# ThrustAmpV1.net
KiCad netlist of a schematic drawn in EAGLE
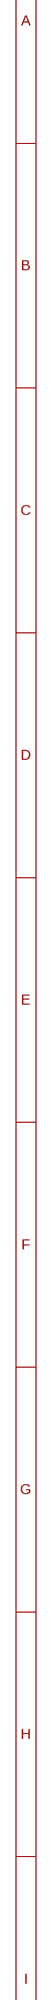
[diagram p0: schematic, sheet 1, part 1 of 2]
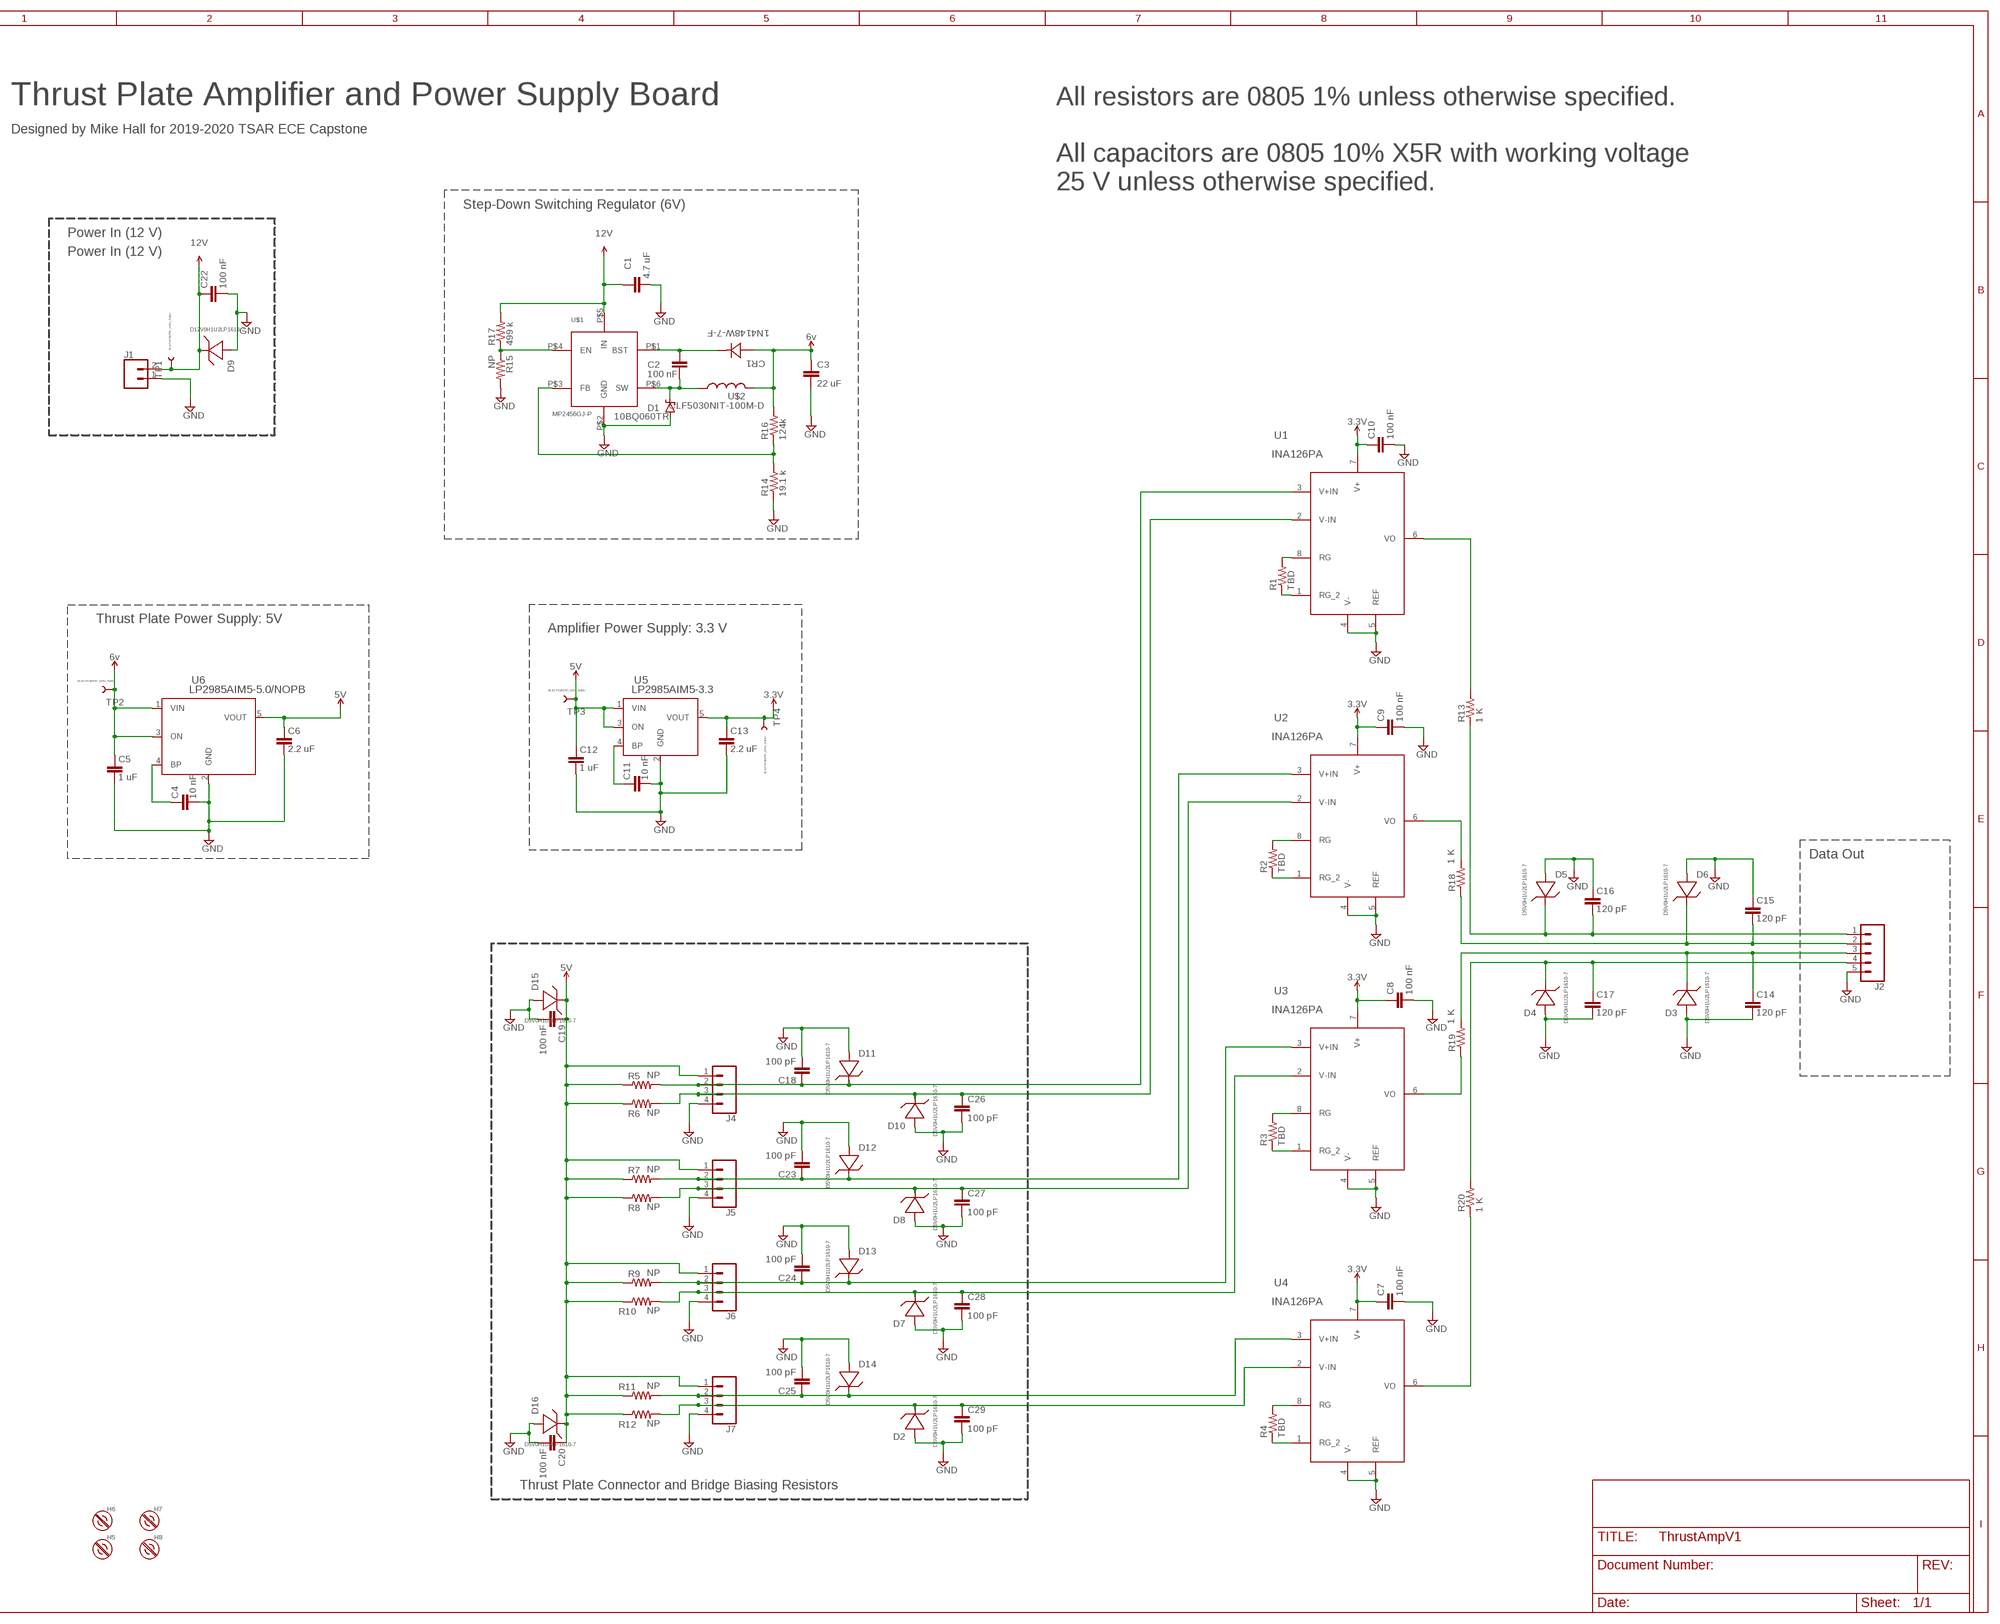
[diagram p1: schematic, sheet 1, part 2 of 2]

(export (version "E")
  (design (tool "Eeschema 10.0.6"))
  (components
    (comp (ref "C1")
      (value "4.7 uF")
      (footprint "eagle-import:C0805")
      (fields (field (name "MFR") "Samsung Electro-Mechanics") (field (name "MPN") "CL21A475KAQNNNE"))
      (libsource (lib "eagle-import") (part "C-EUC0805"))
    )
    (comp (ref "C2")
      (value "100 nF")
      (footprint "eagle-import:C0805")
      (fields (field (name "MFR") "AVX Corporation") (field (name "MPN") "08055D104KAT2A"))
      (libsource (lib "eagle-import") (part "C-EUC0805"))
    )
    (comp (ref "C3")
      (value "22 uF")
      (footprint "eagle-import:C0805")
      (fields (field (name "MFR") "Samsung Electro-Mechanics") (field (name "MPN") "CL21A226KPCLRNC"))
      (libsource (lib "eagle-import") (part "C-EUC0805"))
    )
    (comp (ref "C4")
      (value "10 nF")
      (footprint "eagle-import:C0805")
      (fields (field (name "MFR") "TDK Corporation") (field (name "MPN") "C2012X5R2E103K125AA"))
      (libsource (lib "eagle-import") (part "C-EUC0805"))
    )
    (comp (ref "C5")
      (value "1 uF")
      (footprint "eagle-import:C0805")
      (fields (field (name "MFR") "Samsung Electro-Mechanics") (field (name "MPN") "CL21A105KACLNNC"))
      (libsource (lib "eagle-import") (part "C-EUC0805"))
    )
    (comp (ref "C6")
      (value "2.2 uF")
      (footprint "eagle-import:C0805")
      (fields (field (name "MFR") "Samsung Electro-Mechanics") (field (name "MPN") "CL21A225KAFNNNG"))
      (libsource (lib "eagle-import") (part "C-EUC0805"))
    )
    (comp (ref "C7")
      (value "100 nF")
      (footprint "eagle-import:C0805K")
      (fields (field (name "MFR") "AVX Corporation") (field (name "MPN") "08055D104KAT2A"))
      (libsource (lib "eagle-import") (part "C-EUC0805K"))
    )
    (comp (ref "C8")
      (value "100 nF")
      (footprint "eagle-import:C0805K")
      (fields (field (name "MFR") "AVX Corporation") (field (name "MPN") "08055D104KAT2A"))
      (libsource (lib "eagle-import") (part "C-EUC0805K"))
    )
    (comp (ref "C9")
      (value "100 nF")
      (footprint "eagle-import:C0805K")
      (fields (field (name "MFR") "AVX Corporation") (field (name "MPN") "08055D104KAT2A"))
      (libsource (lib "eagle-import") (part "C-EUC0805K"))
    )
    (comp (ref "C10")
      (value "100 nF")
      (footprint "eagle-import:C0805K")
      (fields (field (name "MFR") "AVX Corporation") (field (name "MPN") "08055D104KAT2A"))
      (libsource (lib "eagle-import") (part "C-EUC0805K"))
    )
    (comp (ref "C11")
      (value "10 nF")
      (footprint "eagle-import:C0805")
      (fields (field (name "MFR") "TDK Corporation") (field (name "MPN") "C2012X5R2E103K125AA"))
      (libsource (lib "eagle-import") (part "C-EUC0805"))
    )
    (comp (ref "C12")
      (value "1 uF")
      (footprint "eagle-import:C0805")
      (fields (field (name "MFR") "Samsung Electro-Mechanics") (field (name "MPN") "CL21A105KACLNNC"))
      (libsource (lib "eagle-import") (part "C-EUC0805"))
    )
    (comp (ref "C13")
      (value "2.2 uF")
      (footprint "eagle-import:C0805")
      (fields (field (name "MFR") "Samsung Electro-Mechanics") (field (name "MPN") "CL21A225KAFNNNG"))
      (libsource (lib "eagle-import") (part "C-EUC0805"))
    )
    (comp (ref "C14")
      (value "120 pF")
      (footprint "eagle-import:C0805")
      (fields (field (name "MFR") "KEMET") (field (name "MPN") "C0805C121KDRACTU"))
      (libsource (lib "eagle-import") (part "C-EUC0805"))
    )
    (comp (ref "C15")
      (value "120 pF")
      (footprint "eagle-import:C0805")
      (fields (field (name "MFR") "KEMET") (field (name "MPN") "C0805C121KDRACTU"))
      (libsource (lib "eagle-import") (part "C-EUC0805"))
    )
    (comp (ref "C16")
      (value "120 pF")
      (footprint "eagle-import:C0805")
      (fields (field (name "MFR") "KEMET") (field (name "MPN") "C0805C121KDRACTU"))
      (libsource (lib "eagle-import") (part "C-EUC0805"))
    )
    (comp (ref "C17")
      (value "120 pF")
      (footprint "eagle-import:C0805")
      (fields (field (name "MFR") "KEMET") (field (name "MPN") "C0805C121KDRACTU"))
      (libsource (lib "eagle-import") (part "C-EUC0805"))
    )
    (comp (ref "C18")
      (value "100 pF")
      (footprint "eagle-import:C0805K")
      (fields (field (name "MFR") "Würth Elektronik") (field (name "MPN") "885012207054"))
      (libsource (lib "eagle-import") (part "C-EUC0805K"))
    )
    (comp (ref "C19")
      (value "100 nF")
      (footprint "eagle-import:C0805K")
      (fields (field (name "MFR") "AVX Corporation") (field (name "MPN") "08055D104KAT2A"))
      (libsource (lib "eagle-import") (part "C-EUC0805K"))
    )
    (comp (ref "C20")
      (value "100 nF")
      (footprint "eagle-import:C0805K")
      (fields (field (name "MFR") "AVX Corporation") (field (name "MPN") "08055D104KAT2A"))
      (libsource (lib "eagle-import") (part "C-EUC0805K"))
    )
    (comp (ref "C22")
      (value "100 nF")
      (footprint "eagle-import:C0805K")
      (fields (field (name "MFR") "AVX Corporation") (field (name "MPN") "08055D104KAT2A"))
      (libsource (lib "eagle-import") (part "C-EUC0805K"))
    )
    (comp (ref "C23")
      (value "100 pF")
      (footprint "eagle-import:C0805K")
      (fields (field (name "MFR") "Würth Elektronik") (field (name "MPN") "885012207054"))
      (libsource (lib "eagle-import") (part "C-EUC0805K"))
    )
    (comp (ref "C24")
      (value "100 pF")
      (footprint "eagle-import:C0805K")
      (fields (field (name "MFR") "Würth Elektronik") (field (name "MPN") "885012207054"))
      (libsource (lib "eagle-import") (part "C-EUC0805K"))
    )
    (comp (ref "C25")
      (value "100 pF")
      (footprint "eagle-import:C0805K")
      (fields (field (name "MFR") "Würth Elektronik") (field (name "MPN") "885012207054"))
      (libsource (lib "eagle-import") (part "C-EUC0805K"))
    )
    (comp (ref "C26")
      (value "100 pF")
      (footprint "eagle-import:C0805K")
      (fields (field (name "MFR") "Würth Elektronik") (field (name "MPN") "885012207054"))
      (libsource (lib "eagle-import") (part "C-EUC0805K"))
    )
    (comp (ref "C27")
      (value "100 pF")
      (footprint "eagle-import:C0805K")
      (fields (field (name "MFR") "Würth Elektronik") (field (name "MPN") "885012207054"))
      (libsource (lib "eagle-import") (part "C-EUC0805K"))
    )
    (comp (ref "C28")
      (value "100 pF")
      (footprint "eagle-import:C0805K")
      (fields (field (name "MFR") "Würth Elektronik") (field (name "MPN") "885012207054"))
      (libsource (lib "eagle-import") (part "C-EUC0805K"))
    )
    (comp (ref "C29")
      (value "100 pF")
      (footprint "eagle-import:C0805K")
      (fields (field (name "MFR") "Würth Elektronik") (field (name "MPN") "885012207054"))
      (libsource (lib "eagle-import") (part "C-EUC0805K"))
    )
    (comp (ref "CR1")
      (value "1N4148W-7-F")
      (footprint "eagle-import:SOD123")
      (fields
        (field (name "MFR") "Diodes Incorporated")
        (field (name "COPYRIGHT") "Copyright (C) 2016 Accelerated Designs. All rights reserved")
      )
      (libsource (lib "eagle-import") (part "1N4148W-7-F"))
    )
    (comp (ref "D1")
      (value "10BQ060TR")
      (footprint "eagle-import:SMB")
      (fields (field (name "MFR") "SMC Diode Solutions"))
      (libsource (lib "eagle-import") (part "SCHOTTKY-DIODESMD"))
    )
    (comp (ref "D2")
      (value "D5V0H1U2LP1610-7")
      (footprint "eagle-import:0603DIODE")
      (fields (field (name "MFR") "Diodes Incorporated"))
      (libsource (lib "eagle-import") (part "D5V0H1U2LP1610-7"))
    )
    (comp (ref "D3")
      (value "D5V0H1U2LP1610-7")
      (footprint "eagle-import:0603DIODE")
      (fields (field (name "MFR") "Diodes Incorporated"))
      (libsource (lib "eagle-import") (part "D5V0H1U2LP1610-7"))
    )
    (comp (ref "D4")
      (value "D5V0H1U2LP1610-7")
      (footprint "eagle-import:0603DIODE")
      (fields (field (name "MFR") "Diodes Incorporated"))
      (libsource (lib "eagle-import") (part "D5V0H1U2LP1610-7"))
    )
    (comp (ref "D5")
      (value "D5V0H1U2LP1610-7")
      (footprint "eagle-import:0603DIODE")
      (fields (field (name "MFR") "Diodes Incorporated"))
      (libsource (lib "eagle-import") (part "D5V0H1U2LP1610-7"))
    )
    (comp (ref "D6")
      (value "D5V0H1U2LP1610-7")
      (footprint "eagle-import:0603DIODE")
      (fields (field (name "MFR") "Diodes Incorporated"))
      (libsource (lib "eagle-import") (part "D5V0H1U2LP1610-7"))
    )
    (comp (ref "D7")
      (value "D5V0H1U2LP1610-7")
      (footprint "eagle-import:0603DIODE")
      (fields (field (name "MFR") "Diodes Incorporated"))
      (libsource (lib "eagle-import") (part "D5V0H1U2LP1610-7"))
    )
    (comp (ref "D8")
      (value "D5V0H1U2LP1610-7")
      (footprint "eagle-import:0603DIODE")
      (fields (field (name "MFR") "Diodes Incorporated"))
      (libsource (lib "eagle-import") (part "D5V0H1U2LP1610-7"))
    )
    (comp (ref "D9")
      (value "D12V0H1U2LP1610-70603DIODE12V")
      (footprint "eagle-import:0603DIODE")
      (fields (field (name "MFR") "Diodes Incorporated") (field (name "MPN") "D12V0H1U2LP1610-7"))
      (libsource (lib "eagle-import") (part "D12V0H1U2LP1610-70603DIODE12V"))
    )
    (comp (ref "D10")
      (value "D5V0H1U2LP1610-7")
      (footprint "eagle-import:0603DIODE")
      (fields (field (name "MFR") "Diodes Incorporated"))
      (libsource (lib "eagle-import") (part "D5V0H1U2LP1610-7"))
    )
    (comp (ref "D11")
      (value "D5V0H1U2LP1610-7")
      (footprint "eagle-import:0603DIODE")
      (fields (field (name "MFR") "Diodes Incorporated"))
      (libsource (lib "eagle-import") (part "D5V0H1U2LP1610-7"))
    )
    (comp (ref "D12")
      (value "D5V0H1U2LP1610-7")
      (footprint "eagle-import:0603DIODE")
      (fields (field (name "MFR") "Diodes Incorporated"))
      (libsource (lib "eagle-import") (part "D5V0H1U2LP1610-7"))
    )
    (comp (ref "D13")
      (value "D5V0H1U2LP1610-7")
      (footprint "eagle-import:0603DIODE")
      (fields (field (name "MFR") "Diodes Incorporated"))
      (libsource (lib "eagle-import") (part "D5V0H1U2LP1610-7"))
    )
    (comp (ref "D14")
      (value "D5V0H1U2LP1610-7")
      (footprint "eagle-import:0603DIODE")
      (fields (field (name "MFR") "Diodes Incorporated"))
      (libsource (lib "eagle-import") (part "D5V0H1U2LP1610-7"))
    )
    (comp (ref "D15")
      (value "D5V0H1U2LP1610-7")
      (footprint "eagle-import:0603DIODE")
      (fields (field (name "MFR") "Diodes Incorporated"))
      (libsource (lib "eagle-import") (part "D5V0H1U2LP1610-7"))
    )
    (comp (ref "D16")
      (value "D5V0H1U2LP1610-7")
      (footprint "eagle-import:0603DIODE")
      (fields (field (name "MFR") "Diodes Incorporated"))
      (libsource (lib "eagle-import") (part "D5V0H1U2LP1610-7"))
    )
    (comp (ref "H5")
      (value "#4-BARE_MOUNTING_HOLE/.300")
      (footprint "eagle-import:#4_.300-BARE+STD_NUT_OR_STAR_WASHER")
      (libsource (lib "eagle-import") (part "#4-BARE_MOUNTING_HOLE/.300"))
    )
    (comp (ref "H6")
      (value "#4-BARE_MOUNTING_HOLE/.300")
      (footprint "eagle-import:#4_.300-BARE+STD_NUT_OR_STAR_WASHER")
      (libsource (lib "eagle-import") (part "#4-BARE_MOUNTING_HOLE/.300"))
    )
    (comp (ref "H7")
      (value "#4-BARE_MOUNTING_HOLE/.300")
      (footprint "eagle-import:#4_.300-BARE+STD_NUT_OR_STAR_WASHER")
      (libsource (lib "eagle-import") (part "#4-BARE_MOUNTING_HOLE/.300"))
    )
    (comp (ref "H8")
      (value "#4-BARE_MOUNTING_HOLE/.300")
      (footprint "eagle-import:#4_.300-BARE+STD_NUT_OR_STAR_WASHER")
      (libsource (lib "eagle-import") (part "#4-BARE_MOUNTING_HOLE/.300"))
    )
    (comp (ref "J1")
      (value "CONN_02PTH3")
      (footprint "eagle-import:1X02_LONGPADS")
      (fields (field (name "MFR") "Molex") (field (name "MPN") "22232021"))
      (libsource (lib "eagle-import") (part "CONN_02PTH3"))
    )
    (comp (ref "J2")
      (value "CONN_05PTH_LONGPADS")
      (footprint "eagle-import:1X05_LONGPADS")
      (fields (field (name "MFR") "Molex") (field (name "MPN") "0022232051"))
      (libsource (lib "eagle-import") (part "CONN_05PTH_LONGPADS"))
    )
    (comp (ref "J4")
      (value "CONN_04")
      (footprint "eagle-import:1X04")
      (fields (field (name "MFR") "Molex") (field (name "MPN") "0022232041"))
      (libsource (lib "eagle-import") (part "CONN_04"))
    )
    (comp (ref "J5")
      (value "CONN_04")
      (footprint "eagle-import:1X04")
      (fields (field (name "MFR") "Molex") (field (name "MPN") "0022232041"))
      (libsource (lib "eagle-import") (part "CONN_04"))
    )
    (comp (ref "J6")
      (value "CONN_04")
      (footprint "eagle-import:1X04")
      (fields (field (name "MFR") "Molex") (field (name "MPN") "0022232041"))
      (libsource (lib "eagle-import") (part "CONN_04"))
    )
    (comp (ref "J7")
      (value "CONN_04")
      (footprint "eagle-import:1X04")
      (fields (field (name "MFR") "Molex") (field (name "MPN") "0022232041"))
      (libsource (lib "eagle-import") (part "CONN_04"))
    )
    (comp (ref "R1")
      (value "TBD")
      (footprint "eagle-import:R0805")
      (libsource (lib "eagle-import") (part "R-US_R0805"))
    )
    (comp (ref "R2")
      (value "TBD")
      (footprint "eagle-import:R0805")
      (libsource (lib "eagle-import") (part "R-US_R0805"))
    )
    (comp (ref "R3")
      (value "TBD")
      (footprint "eagle-import:R0805")
      (libsource (lib "eagle-import") (part "R-US_R0805"))
    )
    (comp (ref "R4")
      (value "TBD")
      (footprint "eagle-import:R0805")
      (libsource (lib "eagle-import") (part "R-US_R0805"))
    )
    (comp (ref "R5")
      (value "NP")
      (footprint "eagle-import:0207_5V")
      (libsource (lib "eagle-import") (part "R-US_0207/5V"))
    )
    (comp (ref "R6")
      (value "NP")
      (footprint "eagle-import:0207_5V")
      (libsource (lib "eagle-import") (part "R-US_0207/5V"))
    )
    (comp (ref "R7")
      (value "NP")
      (footprint "eagle-import:0207_5V")
      (libsource (lib "eagle-import") (part "R-US_0207/5V"))
    )
    (comp (ref "R8")
      (value "NP")
      (footprint "eagle-import:0207_5V")
      (libsource (lib "eagle-import") (part "R-US_0207/5V"))
    )
    (comp (ref "R9")
      (value "NP")
      (footprint "eagle-import:0207_5V")
      (libsource (lib "eagle-import") (part "R-US_0207/5V"))
    )
    (comp (ref "R10")
      (value "NP")
      (footprint "eagle-import:0207_5V")
      (libsource (lib "eagle-import") (part "R-US_0207/5V"))
    )
    (comp (ref "R11")
      (value "NP")
      (footprint "eagle-import:0207_5V")
      (libsource (lib "eagle-import") (part "R-US_0207/5V"))
    )
    (comp (ref "R12")
      (value "NP")
      (footprint "eagle-import:0207_5V")
      (libsource (lib "eagle-import") (part "R-US_0207/5V"))
    )
    (comp (ref "R13")
      (value "1 K")
      (footprint "eagle-import:R0805")
      (fields (field (name "MFR") "Yageo") (field (name "MPN") "RC0805FR-071KL"))
      (libsource (lib "eagle-import") (part "R-US_R0805"))
    )
    (comp (ref "R14")
      (value "19.1 k")
      (footprint "eagle-import:R0805")
      (fields (field (name "MFR") "Stackpole Electronics Inc") (field (name "MPN") "RNCP0805FTD19K1"))
      (libsource (lib "eagle-import") (part "R-US_R0805"))
    )
    (comp (ref "R15")
      (value "NP")
      (footprint "eagle-import:R0805")
      (libsource (lib "eagle-import") (part "R-US_R0805"))
    )
    (comp (ref "R16")
      (value "124k")
      (footprint "eagle-import:R0805")
      (fields (field (name "MFR") "KOA Speer Electronics, Inc.") (field (name "MPN") "RK73H2ATTD1243F"))
      (libsource (lib "eagle-import") (part "R-US_R0805"))
    )
    (comp (ref "R17")
      (value "499 k")
      (footprint "eagle-import:R0805")
      (fields (field (name "MFR") "KOA Speer Electronics, Inc.") (field (name "MPN") "RK73H2ATTD4993F"))
      (libsource (lib "eagle-import") (part "R-US_R0805"))
    )
    (comp (ref "R18")
      (value "1 K")
      (footprint "eagle-import:R0805")
      (fields (field (name "MFR") "Yageo") (field (name "MPN") "RC0805FR-071KL"))
      (libsource (lib "eagle-import") (part "R-US_R0805"))
    )
    (comp (ref "R19")
      (value "1 K")
      (footprint "eagle-import:R0805")
      (fields (field (name "MFR") "Yageo") (field (name "MPN") "RC0805FR-071KL"))
      (libsource (lib "eagle-import") (part "R-US_R0805"))
    )
    (comp (ref "R20")
      (value "1 K")
      (footprint "eagle-import:R0805")
      (fields (field (name "MFR") "Yageo") (field (name "MPN") "RC0805FR-071KL"))
      (libsource (lib "eagle-import") (part "R-US_R0805"))
    )
    (comp (ref "TP1")
      (value "TEST-POINTTP_15TH_THRU")
      (footprint "eagle-import:TP_15TH")
      (libsource (lib "eagle-import") (part "TEST-POINTTP_15TH_THRU"))
    )
    (comp (ref "TP2")
      (value "TEST-POINTTP_15TH_THRU")
      (footprint "eagle-import:TP_15TH")
      (libsource (lib "eagle-import") (part "TEST-POINTTP_15TH_THRU"))
    )
    (comp (ref "TP3")
      (value "TEST-POINTTP_15TH_THRU")
      (footprint "eagle-import:TP_15TH")
      (libsource (lib "eagle-import") (part "TEST-POINTTP_15TH_THRU"))
    )
    (comp (ref "TP4")
      (value "TEST-POINTTP_15TH_THRU")
      (footprint "eagle-import:TP_15TH")
      (libsource (lib "eagle-import") (part "TEST-POINTTP_15TH_THRU"))
    )
    (comp (ref "U$1")
      (value "MP2456GJ-P")
      (footprint "eagle-import:SOT6")
      (fields (field (name "MFR") "Monolithic Power Systems Inc."))
      (libsource (lib "eagle-import") (part "MP2456GJ-P"))
    )
    (comp (ref "U$2")
      (value "CLF5030NIT-100M-D")
      (footprint "eagle-import:0.209_LX0.197_W(5.30MMX5.00MM)")
      (fields (field (name "MFR") "TDK Corporation"))
      (libsource (lib "eagle-import") (part "CLF5030NIT-100M-D"))
    )
    (comp (ref "U1")
      (value "INA126PA")
      (footprint "eagle-import:P8")
      (fields (field (name "MFR") "Texas Instruments"))
      (libsource (lib "eagle-import") (part "INA126PA"))
    )
    (comp (ref "U2")
      (value "INA126PA")
      (footprint "eagle-import:P8")
      (fields (field (name "MFR") "Texas Instruments"))
      (libsource (lib "eagle-import") (part "INA126PA"))
    )
    (comp (ref "U3")
      (value "INA126PA")
      (footprint "eagle-import:P8")
      (fields (field (name "MFR") "Texas Instruments"))
      (libsource (lib "eagle-import") (part "INA126PA"))
    )
    (comp (ref "U4")
      (value "INA126PA")
      (footprint "eagle-import:P8")
      (fields (field (name "MFR") "Texas Instruments"))
      (libsource (lib "eagle-import") (part "INA126PA"))
    )
    (comp (ref "U5")
      (value "LP2985AIM5-3.3")
      (footprint "eagle-import:MF05A")
      (fields (field (name "MFR") "Texas Instruments") (field (name "MPN") "LP2985AIM5-3.3/NOPB"))
      (libsource (lib "eagle-import") (part "LP2985AIM5-3.3"))
    )
    (comp (ref "U6")
      (value "LP2985AIM5-5.0/NOPB")
      (footprint "eagle-import:MF05A")
      (fields (field (name "MFR") "Texas Instruments"))
      (libsource (lib "eagle-import") (part "LP2985AIM5-5.0/NOPB"))
    )
  )
  (nets
    (net (code "1") (name "3.3V") (class "Default")
      (node (ref "C10") (pin "1") (pinfunction "1_1") (pintype "passive"))
      (node (ref "C13") (pin "1") (pinfunction "1_1") (pintype "passive"))
      (node (ref "C7") (pin "1") (pinfunction "1_1") (pintype "passive"))
      (node (ref "C8") (pin "1") (pinfunction "1_1") (pintype "passive"))
      (node (ref "C9") (pin "1") (pinfunction "1_1") (pintype "passive"))
      (node (ref "TP4") (pin "P$1") (pinfunction "1_P$1") (pintype "bidirectional"))
      (node (ref "U1") (pin "7") (pinfunction "V+_7") (pintype "power_in"))
      (node (ref "U2") (pin "7") (pinfunction "V+_7") (pintype "power_in"))
      (node (ref "U3") (pin "7") (pinfunction "V+_7") (pintype "power_in"))
      (node (ref "U4") (pin "7") (pinfunction "V+_7") (pintype "power_in"))
      (node (ref "U5") (pin "5") (pinfunction "VOUT_5") (pintype "power_in"))
    )
    (net (code "2") (name "5V") (class "Default")
      (node (ref "C12") (pin "1") (pinfunction "1_1") (pintype "passive"))
      (node (ref "C19") (pin "1") (pinfunction "1_1") (pintype "passive"))
      (node (ref "C20") (pin "1") (pinfunction "1_1") (pintype "passive"))
      (node (ref "C6") (pin "1") (pinfunction "1_1") (pintype "passive"))
      (node (ref "D15") (pin "P$2") (pinfunction "P$2_P$2") (pintype "passive"))
      (node (ref "D16") (pin "P$2") (pinfunction "P$2_P$2") (pintype "passive"))
      (node (ref "J4") (pin "1") (pinfunction "1_1") (pintype "passive"))
      (node (ref "J5") (pin "1") (pinfunction "1_1") (pintype "passive"))
      (node (ref "J6") (pin "1") (pinfunction "1_1") (pintype "passive"))
      (node (ref "J7") (pin "1") (pinfunction "1_1") (pintype "passive"))
      (node (ref "R10") (pin "1") (pinfunction "1_1") (pintype "passive"))
      (node (ref "R11") (pin "1") (pinfunction "1_1") (pintype "passive"))
      (node (ref "R12") (pin "1") (pinfunction "1_1") (pintype "passive"))
      (node (ref "R5") (pin "1") (pinfunction "1_1") (pintype "passive"))
      (node (ref "R6") (pin "1") (pinfunction "1_1") (pintype "passive"))
      (node (ref "R7") (pin "1") (pinfunction "1_1") (pintype "passive"))
      (node (ref "R8") (pin "1") (pinfunction "1_1") (pintype "passive"))
      (node (ref "R9") (pin "1") (pinfunction "1_1") (pintype "passive"))
      (node (ref "TP3") (pin "P$1") (pinfunction "1_P$1") (pintype "bidirectional"))
      (node (ref "U5") (pin "1") (pinfunction "VIN_1") (pintype "power_in"))
      (node (ref "U5") (pin "3") (pinfunction "ON_3") (pintype "input"))
      (node (ref "U6") (pin "5") (pinfunction "VOUT_5") (pintype "power_in"))
    )
    (net (code "3") (name "6v") (class "Default")
      (node (ref "C3") (pin "1") (pinfunction "1_1") (pintype "passive"))
      (node (ref "C5") (pin "1") (pinfunction "1_1") (pintype "passive"))
      (node (ref "CR1") (pin "2") (pinfunction "2_2") (pintype "passive"))
      (node (ref "R16") (pin "2") (pinfunction "2_2") (pintype "passive"))
      (node (ref "TP2") (pin "P$1") (pinfunction "1_P$1") (pintype "bidirectional"))
      (node (ref "U$2") (pin "2") (pinfunction "2_2") (pintype "passive"))
      (node (ref "U6") (pin "1") (pinfunction "VIN_1") (pintype "input"))
      (node (ref "U6") (pin "3") (pinfunction "ON_3") (pintype "passive"))
    )
    (net (code "4") (name "12V") (class "Default")
      (node (ref "C1") (pin "1") (pinfunction "1_1") (pintype "passive"))
      (node (ref "C22") (pin "1") (pinfunction "1_1") (pintype "passive"))
      (node (ref "D9") (pin "P$2") (pinfunction "P$2_P$2") (pintype "passive"))
      (node (ref "J1") (pin "2") (pinfunction "2_2") (pintype "passive"))
      (node (ref "R17") (pin "2") (pinfunction "2_2") (pintype "passive"))
      (node (ref "TP1") (pin "P$1") (pinfunction "1_P$1") (pintype "bidirectional"))
      (node (ref "U$1") (pin "P$5") (pinfunction "IN_P$5") (pintype "power_in"))
    )
    (net (code "5") (name "GND") (class "Default")
      (node (ref "C1") (pin "2") (pinfunction "2_2") (pintype "passive"))
      (node (ref "C10") (pin "2") (pinfunction "2_2") (pintype "passive"))
      (node (ref "C11") (pin "2") (pinfunction "2_2") (pintype "passive"))
      (node (ref "C12") (pin "2") (pinfunction "2_2") (pintype "passive"))
      (node (ref "C13") (pin "2") (pinfunction "2_2") (pintype "passive"))
      (node (ref "C14") (pin "2") (pinfunction "2_2") (pintype "passive"))
      (node (ref "C15") (pin "1") (pinfunction "1_1") (pintype "passive"))
      (node (ref "C16") (pin "1") (pinfunction "1_1") (pintype "passive"))
      (node (ref "C17") (pin "2") (pinfunction "2_2") (pintype "passive"))
      (node (ref "C18") (pin "2") (pinfunction "2_2") (pintype "passive"))
      (node (ref "C19") (pin "2") (pinfunction "2_2") (pintype "passive"))
      (node (ref "C20") (pin "2") (pinfunction "2_2") (pintype "passive"))
      (node (ref "C22") (pin "2") (pinfunction "2_2") (pintype "passive"))
      (node (ref "C23") (pin "2") (pinfunction "2_2") (pintype "passive"))
      (node (ref "C24") (pin "2") (pinfunction "2_2") (pintype "passive"))
      (node (ref "C25") (pin "2") (pinfunction "2_2") (pintype "passive"))
      (node (ref "C26") (pin "2") (pinfunction "2_2") (pintype "passive"))
      (node (ref "C27") (pin "2") (pinfunction "2_2") (pintype "passive"))
      (node (ref "C28") (pin "2") (pinfunction "2_2") (pintype "passive"))
      (node (ref "C29") (pin "2") (pinfunction "2_2") (pintype "passive"))
      (node (ref "C3") (pin "2") (pinfunction "2_2") (pintype "passive"))
      (node (ref "C4") (pin "2") (pinfunction "2_2") (pintype "passive"))
      (node (ref "C5") (pin "2") (pinfunction "2_2") (pintype "passive"))
      (node (ref "C6") (pin "2") (pinfunction "2_2") (pintype "passive"))
      (node (ref "C7") (pin "2") (pinfunction "2_2") (pintype "passive"))
      (node (ref "C8") (pin "2") (pinfunction "2_2") (pintype "passive"))
      (node (ref "C9") (pin "2") (pinfunction "2_2") (pintype "passive"))
      (node (ref "D1") (pin "A") (pinfunction "A_A") (pintype "passive"))
      (node (ref "D10") (pin "P$1") (pinfunction "P$1_P$1") (pintype "passive"))
      (node (ref "D11") (pin "P$1") (pinfunction "P$1_P$1") (pintype "passive"))
      (node (ref "D12") (pin "P$1") (pinfunction "P$1_P$1") (pintype "passive"))
      (node (ref "D13") (pin "P$1") (pinfunction "P$1_P$1") (pintype "passive"))
      (node (ref "D14") (pin "P$1") (pinfunction "P$1_P$1") (pintype "passive"))
      (node (ref "D15") (pin "P$1") (pinfunction "P$1_P$1") (pintype "passive"))
      (node (ref "D16") (pin "P$1") (pinfunction "P$1_P$1") (pintype "passive"))
      (node (ref "D2") (pin "P$1") (pinfunction "P$1_P$1") (pintype "passive"))
      (node (ref "D3") (pin "P$1") (pinfunction "P$1_P$1") (pintype "passive"))
      (node (ref "D4") (pin "P$1") (pinfunction "P$1_P$1") (pintype "passive"))
      (node (ref "D5") (pin "P$1") (pinfunction "P$1_P$1") (pintype "passive"))
      (node (ref "D6") (pin "P$1") (pinfunction "P$1_P$1") (pintype "passive"))
      (node (ref "D7") (pin "P$1") (pinfunction "P$1_P$1") (pintype "passive"))
      (node (ref "D8") (pin "P$1") (pinfunction "P$1_P$1") (pintype "passive"))
      (node (ref "D9") (pin "P$1") (pinfunction "P$1_P$1") (pintype "passive"))
      (node (ref "J1") (pin "1") (pinfunction "1_1") (pintype "passive"))
      (node (ref "J2") (pin "5") (pinfunction "5_5") (pintype "passive"))
      (node (ref "J4") (pin "4") (pinfunction "4_4") (pintype "passive"))
      (node (ref "J5") (pin "4") (pinfunction "4_4") (pintype "passive"))
      (node (ref "J6") (pin "4") (pinfunction "4_4") (pintype "passive"))
      (node (ref "J7") (pin "4") (pinfunction "4_4") (pintype "passive"))
      (node (ref "R14") (pin "1") (pinfunction "1_1") (pintype "passive"))
      (node (ref "R15") (pin "2") (pinfunction "2_2") (pintype "passive"))
      (node (ref "U$1") (pin "P$2") (pinfunction "GND_P$2") (pintype "bidirectional"))
      (node (ref "U1") (pin "4") (pinfunction "V-_4") (pintype "power_in"))
      (node (ref "U1") (pin "5") (pinfunction "REF_5") (pintype "passive"))
      (node (ref "U2") (pin "4") (pinfunction "V-_4") (pintype "power_in"))
      (node (ref "U2") (pin "5") (pinfunction "REF_5") (pintype "passive"))
      (node (ref "U3") (pin "4") (pinfunction "V-_4") (pintype "power_in"))
      (node (ref "U3") (pin "5") (pinfunction "REF_5") (pintype "passive"))
      (node (ref "U4") (pin "4") (pinfunction "V-_4") (pintype "power_in"))
      (node (ref "U4") (pin "5") (pinfunction "REF_5") (pintype "passive"))
      (node (ref "U5") (pin "2") (pinfunction "GND_2") (pintype "passive"))
      (node (ref "U6") (pin "2") (pinfunction "GND_2") (pintype "passive"))
    )
    (net (code "6") (name "Net-(C14-Pad1)") (class "Default")
      (node (ref "C14") (pin "1") (pinfunction "1_1") (pintype "passive"))
      (node (ref "D3") (pin "P$2") (pinfunction "P$2_P$2") (pintype "passive"))
      (node (ref "J2") (pin "3") (pinfunction "3_3") (pintype "passive"))
      (node (ref "R19") (pin "2") (pinfunction "2_2") (pintype "passive"))
    )
    (net (code "7") (name "Net-(C15-Pad2)") (class "Default")
      (node (ref "C15") (pin "2") (pinfunction "2_2") (pintype "passive"))
      (node (ref "D6") (pin "P$2") (pinfunction "P$2_P$2") (pintype "passive"))
      (node (ref "J2") (pin "2") (pinfunction "2_2") (pintype "passive"))
      (node (ref "R18") (pin "1") (pinfunction "1_1") (pintype "passive"))
    )
    (net (code "8") (name "Net-(C16-Pad2)") (class "Default")
      (node (ref "C16") (pin "2") (pinfunction "2_2") (pintype "passive"))
      (node (ref "D5") (pin "P$2") (pinfunction "P$2_P$2") (pintype "passive"))
      (node (ref "J2") (pin "1") (pinfunction "1_1") (pintype "passive"))
      (node (ref "R13") (pin "1") (pinfunction "1_1") (pintype "passive"))
    )
    (net (code "9") (name "Net-(C17-Pad1)") (class "Default")
      (node (ref "C17") (pin "1") (pinfunction "1_1") (pintype "passive"))
      (node (ref "D4") (pin "P$2") (pinfunction "P$2_P$2") (pintype "passive"))
      (node (ref "J2") (pin "4") (pinfunction "4_4") (pintype "passive"))
      (node (ref "R20") (pin "2") (pinfunction "2_2") (pintype "passive"))
    )
    (net (code "10") (name "Net-(U$1-BST)") (class "Default")
      (node (ref "C2") (pin "1") (pinfunction "1_1") (pintype "passive"))
      (node (ref "CR1") (pin "1") (pinfunction "1_1") (pintype "passive"))
      (node (ref "U$1") (pin "P$1") (pinfunction "BST_P$1") (pintype "bidirectional"))
    )
    (net (code "11") (name "Net-(U$1-EN)") (class "Default")
      (node (ref "R15") (pin "1") (pinfunction "1_1") (pintype "passive"))
      (node (ref "R17") (pin "1") (pinfunction "1_1") (pintype "passive"))
      (node (ref "U$1") (pin "P$4") (pinfunction "EN_P$4") (pintype "input"))
    )
    (net (code "12") (name "Net-(U$1-FB)") (class "Default")
      (node (ref "R14") (pin "2") (pinfunction "2_2") (pintype "passive"))
      (node (ref "R16") (pin "1") (pinfunction "1_1") (pintype "passive"))
      (node (ref "U$1") (pin "P$3") (pinfunction "FB_P$3") (pintype "bidirectional"))
    )
    (net (code "13") (name "Net-(U$1-SW)") (class "Default")
      (node (ref "C2") (pin "2") (pinfunction "2_2") (pintype "passive"))
      (node (ref "D1") (pin "C") (pinfunction "C_C") (pintype "passive"))
      (node (ref "U$1") (pin "P$6") (pinfunction "SW_P$6") (pintype "bidirectional"))
      (node (ref "U$2") (pin "1") (pinfunction "1_1") (pintype "passive"))
    )
    (net (code "14") (name "Net-(U1-RG)") (class "Default")
      (node (ref "R1") (pin "2") (pinfunction "2_2") (pintype "passive"))
      (node (ref "U1") (pin "8") (pinfunction "RG_8") (pintype "passive"))
    )
    (net (code "15") (name "Net-(U1-RG_2)") (class "Default")
      (node (ref "R1") (pin "1") (pinfunction "1_1") (pintype "passive"))
      (node (ref "U1") (pin "1") (pinfunction "RG_2_1") (pintype "passive"))
    )
    (net (code "16") (name "Net-(U1-V+IN)") (class "Default")
      (node (ref "C18") (pin "1") (pinfunction "1_1") (pintype "passive"))
      (node (ref "D11") (pin "P$2") (pinfunction "P$2_P$2") (pintype "passive"))
      (node (ref "J4") (pin "2") (pinfunction "2_2") (pintype "passive"))
      (node (ref "R5") (pin "2") (pinfunction "2_2") (pintype "passive"))
      (node (ref "U1") (pin "3") (pinfunction "V+IN_3") (pintype "input"))
    )
    (net (code "17") (name "Net-(U1-V-IN)") (class "Default")
      (node (ref "C26") (pin "1") (pinfunction "1_1") (pintype "passive"))
      (node (ref "D10") (pin "P$2") (pinfunction "P$2_P$2") (pintype "passive"))
      (node (ref "J4") (pin "3") (pinfunction "3_3") (pintype "passive"))
      (node (ref "R6") (pin "2") (pinfunction "2_2") (pintype "passive"))
      (node (ref "U1") (pin "2") (pinfunction "V-IN_2") (pintype "input"))
    )
    (net (code "18") (name "Net-(U1-VO)") (class "Default")
      (node (ref "R13") (pin "2") (pinfunction "2_2") (pintype "passive"))
      (node (ref "U1") (pin "6") (pinfunction "VO_6") (pintype "output"))
    )
    (net (code "19") (name "Net-(U2-RG)") (class "Default")
      (node (ref "R2") (pin "2") (pinfunction "2_2") (pintype "passive"))
      (node (ref "U2") (pin "8") (pinfunction "RG_8") (pintype "passive"))
    )
    (net (code "20") (name "Net-(U2-RG_2)") (class "Default")
      (node (ref "R2") (pin "1") (pinfunction "1_1") (pintype "passive"))
      (node (ref "U2") (pin "1") (pinfunction "RG_2_1") (pintype "passive"))
    )
    (net (code "21") (name "Net-(U2-V+IN)") (class "Default")
      (node (ref "C23") (pin "1") (pinfunction "1_1") (pintype "passive"))
      (node (ref "D12") (pin "P$2") (pinfunction "P$2_P$2") (pintype "passive"))
      (node (ref "J5") (pin "2") (pinfunction "2_2") (pintype "passive"))
      (node (ref "R7") (pin "2") (pinfunction "2_2") (pintype "passive"))
      (node (ref "U2") (pin "3") (pinfunction "V+IN_3") (pintype "input"))
    )
    (net (code "22") (name "Net-(U2-V-IN)") (class "Default")
      (node (ref "C27") (pin "1") (pinfunction "1_1") (pintype "passive"))
      (node (ref "D8") (pin "P$2") (pinfunction "P$2_P$2") (pintype "passive"))
      (node (ref "J5") (pin "3") (pinfunction "3_3") (pintype "passive"))
      (node (ref "R8") (pin "2") (pinfunction "2_2") (pintype "passive"))
      (node (ref "U2") (pin "2") (pinfunction "V-IN_2") (pintype "input"))
    )
    (net (code "23") (name "Net-(U2-VO)") (class "Default")
      (node (ref "R18") (pin "2") (pinfunction "2_2") (pintype "passive"))
      (node (ref "U2") (pin "6") (pinfunction "VO_6") (pintype "output"))
    )
    (net (code "24") (name "Net-(U3-RG)") (class "Default")
      (node (ref "R3") (pin "2") (pinfunction "2_2") (pintype "passive"))
      (node (ref "U3") (pin "8") (pinfunction "RG_8") (pintype "passive"))
    )
    (net (code "25") (name "Net-(U3-RG_2)") (class "Default")
      (node (ref "R3") (pin "1") (pinfunction "1_1") (pintype "passive"))
      (node (ref "U3") (pin "1") (pinfunction "RG_2_1") (pintype "passive"))
    )
    (net (code "26") (name "Net-(U3-V+IN)") (class "Default")
      (node (ref "C24") (pin "1") (pinfunction "1_1") (pintype "passive"))
      (node (ref "D13") (pin "P$2") (pinfunction "P$2_P$2") (pintype "passive"))
      (node (ref "J6") (pin "2") (pinfunction "2_2") (pintype "passive"))
      (node (ref "R9") (pin "2") (pinfunction "2_2") (pintype "passive"))
      (node (ref "U3") (pin "3") (pinfunction "V+IN_3") (pintype "input"))
    )
    (net (code "27") (name "Net-(U3-V-IN)") (class "Default")
      (node (ref "C28") (pin "1") (pinfunction "1_1") (pintype "passive"))
      (node (ref "D7") (pin "P$2") (pinfunction "P$2_P$2") (pintype "passive"))
      (node (ref "J6") (pin "3") (pinfunction "3_3") (pintype "passive"))
      (node (ref "R10") (pin "2") (pinfunction "2_2") (pintype "passive"))
      (node (ref "U3") (pin "2") (pinfunction "V-IN_2") (pintype "input"))
    )
    (net (code "28") (name "Net-(U3-VO)") (class "Default")
      (node (ref "R19") (pin "1") (pinfunction "1_1") (pintype "passive"))
      (node (ref "U3") (pin "6") (pinfunction "VO_6") (pintype "output"))
    )
    (net (code "29") (name "Net-(U4-RG)") (class "Default")
      (node (ref "R4") (pin "2") (pinfunction "2_2") (pintype "passive"))
      (node (ref "U4") (pin "8") (pinfunction "RG_8") (pintype "passive"))
    )
    (net (code "30") (name "Net-(U4-RG_2)") (class "Default")
      (node (ref "R4") (pin "1") (pinfunction "1_1") (pintype "passive"))
      (node (ref "U4") (pin "1") (pinfunction "RG_2_1") (pintype "passive"))
    )
    (net (code "31") (name "Net-(U4-V+IN)") (class "Default")
      (node (ref "C25") (pin "1") (pinfunction "1_1") (pintype "passive"))
      (node (ref "D14") (pin "P$2") (pinfunction "P$2_P$2") (pintype "passive"))
      (node (ref "J7") (pin "2") (pinfunction "2_2") (pintype "passive"))
      (node (ref "R11") (pin "2") (pinfunction "2_2") (pintype "passive"))
      (node (ref "U4") (pin "3") (pinfunction "V+IN_3") (pintype "input"))
    )
    (net (code "32") (name "Net-(U4-V-IN)") (class "Default")
      (node (ref "C29") (pin "1") (pinfunction "1_1") (pintype "passive"))
      (node (ref "D2") (pin "P$2") (pinfunction "P$2_P$2") (pintype "passive"))
      (node (ref "J7") (pin "3") (pinfunction "3_3") (pintype "passive"))
      (node (ref "R12") (pin "2") (pinfunction "2_2") (pintype "passive"))
      (node (ref "U4") (pin "2") (pinfunction "V-IN_2") (pintype "input"))
    )
    (net (code "33") (name "Net-(U4-VO)") (class "Default")
      (node (ref "R20") (pin "1") (pinfunction "1_1") (pintype "passive"))
      (node (ref "U4") (pin "6") (pinfunction "VO_6") (pintype "output"))
    )
    (net (code "34") (name "Net-(U5-BP)") (class "Default")
      (node (ref "C11") (pin "1") (pinfunction "1_1") (pintype "passive"))
      (node (ref "U5") (pin "4") (pinfunction "BP_4") (pintype "passive"))
    )
    (net (code "35") (name "Net-(U6-BP)") (class "Default")
      (node (ref "C4") (pin "1") (pinfunction "1_1") (pintype "passive"))
      (node (ref "U6") (pin "4") (pinfunction "BP_4") (pintype "passive"))
    )
  )
)
